# rtc.net
KiCad netlist of a schematic drawn in EAGLE
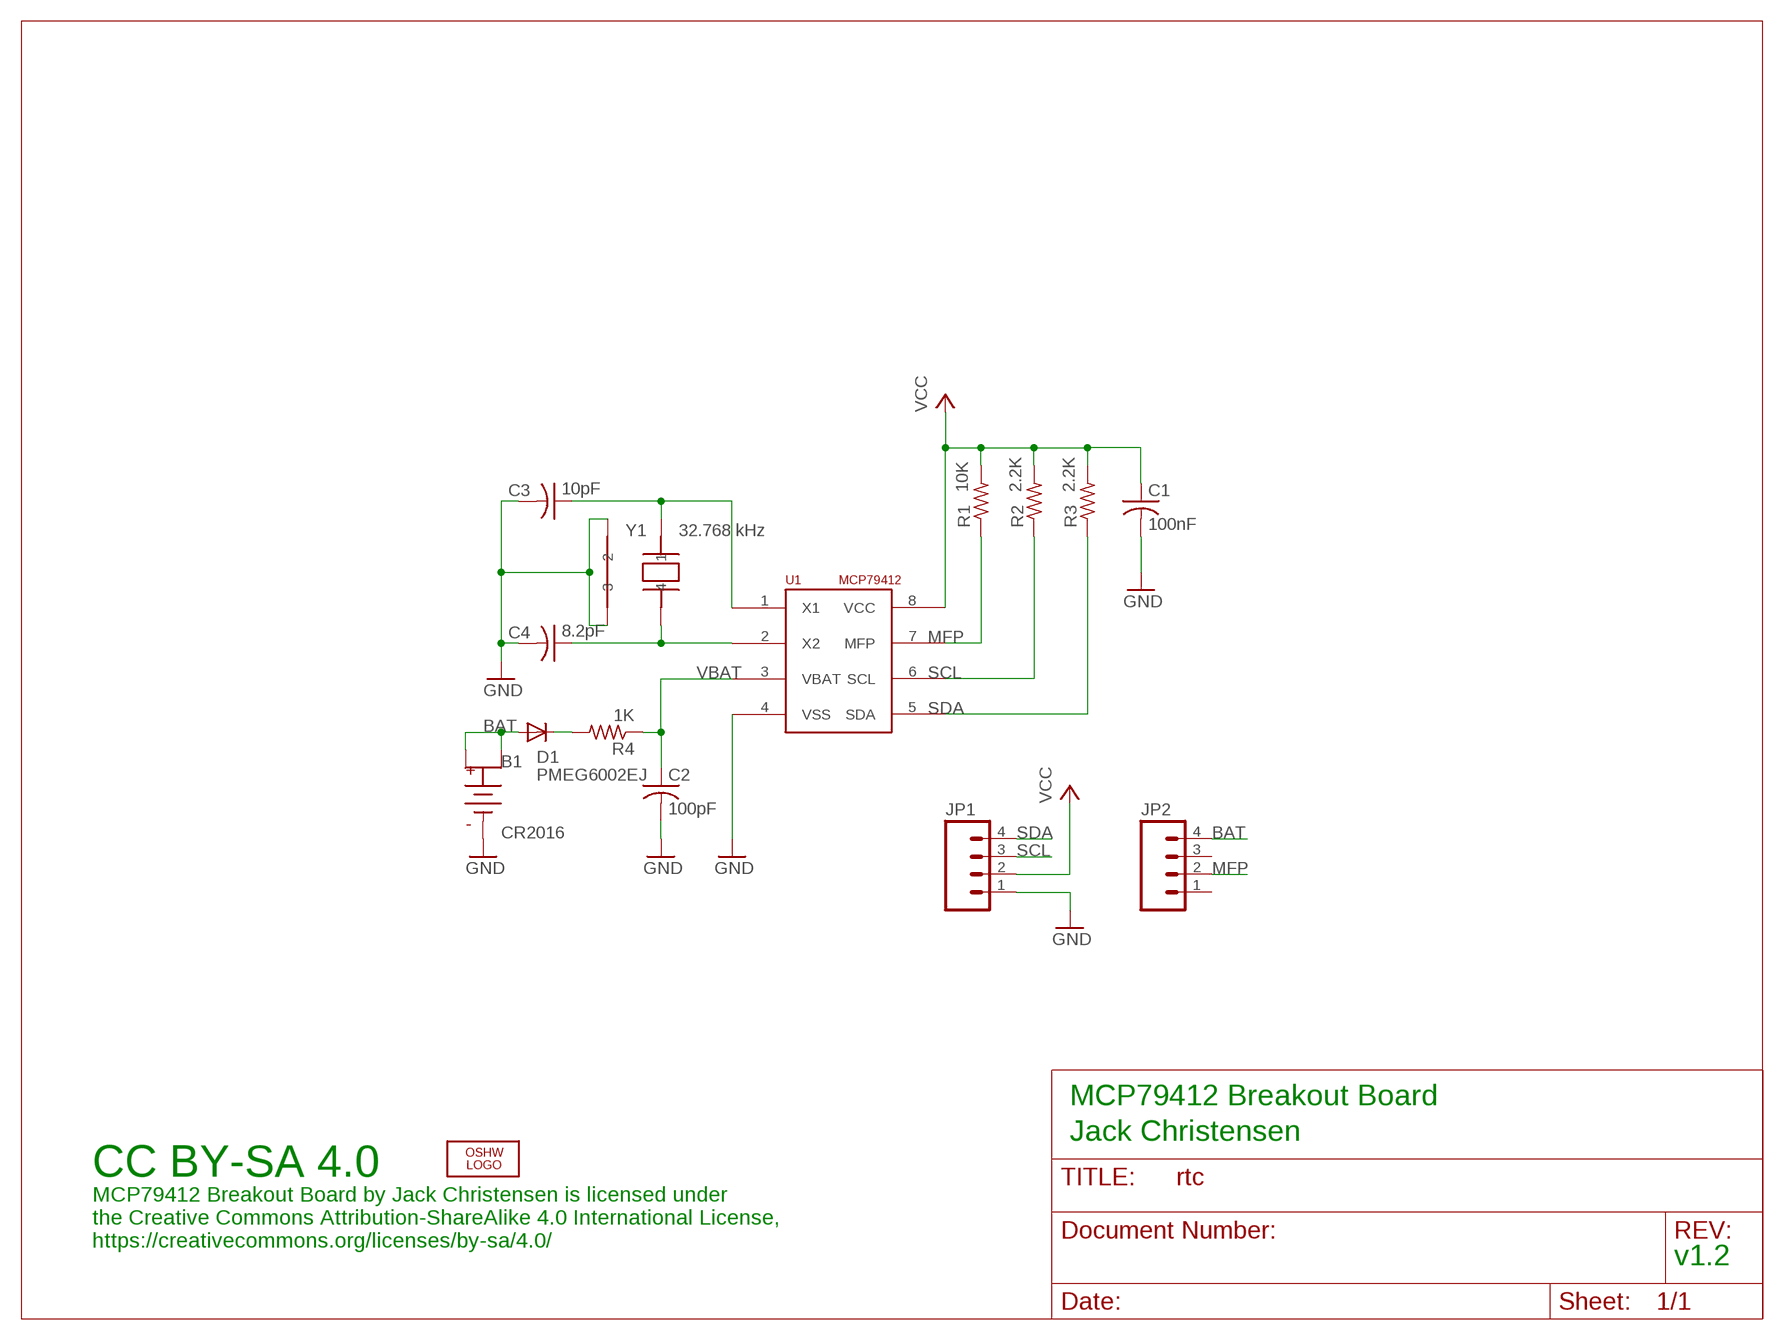
[diagram p0: schematic, sheet 1]

(export (version "E")
  (design (tool "Eeschema 10.0.6"))
  (components
    (comp (ref "B1")
      (value "CR2016")
      (footprint "eagle-import:BAT-HLD-002-SMT")
      (libsource (lib "eagle-import") (part "COIN-CELL-2016-SMT"))
    )
    (comp (ref "C1")
      (value "100nF")
      (footprint "eagle-import:M0805")
      (libsource (lib "eagle-import") (part "C-USM0805"))
    )
    (comp (ref "C2")
      (value "100pF")
      (footprint "eagle-import:M0805")
      (libsource (lib "eagle-import") (part "C-USM0805"))
    )
    (comp (ref "C3")
      (value "10pF")
      (footprint "eagle-import:M0805")
      (libsource (lib "eagle-import") (part "C-USM0805"))
    )
    (comp (ref "C4")
      (value "8.2pF")
      (footprint "eagle-import:M0805")
      (libsource (lib "eagle-import") (part "C-USM0805"))
    )
    (comp (ref "D1")
      (value "PMEG6002EJ")
      (footprint "eagle-import:SOD-323F-A")
      (libsource (lib "eagle-import") (part "DIODESOD-323F-A"))
    )
    (comp (ref "JP1")
      (value "M04LOCK")
      (footprint "eagle-import:1X04_LOCK")
      (libsource (lib "eagle-import") (part "M04LOCK"))
    )
    (comp (ref "JP2")
      (value "M04LOCK")
      (footprint "eagle-import:1X04_LOCK")
      (libsource (lib "eagle-import") (part "M04LOCK"))
    )
    (comp (ref "LOGO2")
      (value "OSHW_LOGO_8MILX0150-NT")
      (footprint "eagle-import:OSHW_8X150_NOTEXT")
      (libsource (lib "eagle-import") (part "OSHW_LOGO_8MILX0150-NT"))
    )
    (comp (ref "R1")
      (value "10K")
      (footprint "eagle-import:M0805")
      (libsource (lib "eagle-import") (part "R-US_M0805"))
    )
    (comp (ref "R2")
      (value "2.2K")
      (footprint "eagle-import:M0805")
      (libsource (lib "eagle-import") (part "R-US_M0805"))
    )
    (comp (ref "R3")
      (value "2.2K")
      (footprint "eagle-import:M0805")
      (libsource (lib "eagle-import") (part "R-US_M0805"))
    )
    (comp (ref "R4")
      (value "1K")
      (footprint "eagle-import:M0805")
      (libsource (lib "eagle-import") (part "R-US_M0805"))
    )
    (comp (ref "U1")
      (value "MCP79412")
      (footprint "eagle-import:SO08")
      (libsource (lib "eagle-import") (part "MCP7941X-SOIC-8"))
    )
    (comp (ref "Y1")
      (value "32.768 kHz")
      (footprint "eagle-import:CRYSTAL-CITIZEN-CM2XXC")
      (libsource (lib "eagle-import") (part "CRYSTAL-CITIZEN-CM2XXC"))
    )
  )
  (nets
    (net (code "1") (name "/BAT") (class "Default")
      (node (ref "B1") (pin "POS1") (pinfunction "POS1_POS1") (pintype "passive"))
      (node (ref "B1") (pin "POS2") (pinfunction "POS2_POS2") (pintype "passive"))
      (node (ref "D1") (pin "A") (pinfunction "A_A") (pintype "passive"))
      (node (ref "JP2") (pin "4") (pinfunction "4_4") (pintype "passive"))
    )
    (net (code "2") (name "/MFP") (class "Default")
      (node (ref "JP2") (pin "2") (pinfunction "2_2") (pintype "passive"))
      (node (ref "R1") (pin "1") (pinfunction "1_1") (pintype "passive"))
      (node (ref "U1") (pin "7") (pinfunction "MFP_7") (pintype "passive"))
    )
    (net (code "3") (name "/SCL") (class "Default")
      (node (ref "JP1") (pin "3") (pinfunction "3_3") (pintype "passive"))
      (node (ref "R2") (pin "1") (pinfunction "1_1") (pintype "passive"))
      (node (ref "U1") (pin "6") (pinfunction "SCL_6") (pintype "passive"))
    )
    (net (code "4") (name "/SDA") (class "Default")
      (node (ref "JP1") (pin "4") (pinfunction "4_4") (pintype "passive"))
      (node (ref "R3") (pin "1") (pinfunction "1_1") (pintype "passive"))
      (node (ref "U1") (pin "5") (pinfunction "SDA_5") (pintype "passive"))
    )
    (net (code "5") (name "/VBAT") (class "Default")
      (node (ref "C2") (pin "1") (pinfunction "1_1") (pintype "passive"))
      (node (ref "R4") (pin "1") (pinfunction "1_1") (pintype "passive"))
      (node (ref "U1") (pin "3") (pinfunction "VBAT_3") (pintype "passive"))
    )
    (net (code "6") (name "GND") (class "Default")
      (node (ref "B1") (pin "NEG") (pinfunction "B-_NEG") (pintype "passive"))
      (node (ref "C1") (pin "2") (pinfunction "2_2") (pintype "passive"))
      (node (ref "C2") (pin "2") (pinfunction "2_2") (pintype "passive"))
      (node (ref "C3") (pin "2") (pinfunction "2_2") (pintype "passive"))
      (node (ref "C4") (pin "2") (pinfunction "2_2") (pintype "passive"))
      (node (ref "JP1") (pin "1") (pinfunction "1_1") (pintype "passive"))
      (node (ref "U1") (pin "4") (pinfunction "VSS_4") (pintype "passive"))
      (node (ref "Y1") (pin "P$2") (pinfunction "2_P$2") (pintype "passive"))
      (node (ref "Y1") (pin "P$3") (pinfunction "3_P$3") (pintype "passive"))
    )
    (net (code "7") (name "Net-(D1-PadK)") (class "Default")
      (node (ref "D1") (pin "K") (pinfunction "K_K") (pintype "passive"))
      (node (ref "R4") (pin "2") (pinfunction "2_2") (pintype "passive"))
    )
    (net (code "8") (name "Net-(U1-X1)") (class "Default")
      (node (ref "C3") (pin "1") (pinfunction "1_1") (pintype "passive"))
      (node (ref "U1") (pin "1") (pinfunction "X1_1") (pintype "passive"))
      (node (ref "Y1") (pin "P$1") (pinfunction "1_P$1") (pintype "passive"))
    )
    (net (code "9") (name "Net-(U1-X2)") (class "Default")
      (node (ref "C4") (pin "1") (pinfunction "1_1") (pintype "passive"))
      (node (ref "U1") (pin "2") (pinfunction "X2_2") (pintype "passive"))
      (node (ref "Y1") (pin "P$4") (pinfunction "4_P$4") (pintype "passive"))
    )
    (net (code "10") (name "VCC") (class "Default")
      (node (ref "C1") (pin "1") (pinfunction "1_1") (pintype "passive"))
      (node (ref "JP1") (pin "2") (pinfunction "2_2") (pintype "passive"))
      (node (ref "R1") (pin "2") (pinfunction "2_2") (pintype "passive"))
      (node (ref "R2") (pin "2") (pinfunction "2_2") (pintype "passive"))
      (node (ref "R3") (pin "2") (pinfunction "2_2") (pintype "passive"))
      (node (ref "U1") (pin "8") (pinfunction "VCC_8") (pintype "passive"))
    )
    (net (code "11") (name "unconnected-(JP2-Pad1)") (class "Default")
      (node (ref "JP2") (pin "1") (pinfunction "1_1") (pintype "passive"))
    )
    (net (code "12") (name "unconnected-(JP2-Pad3)") (class "Default")
      (node (ref "JP2") (pin "3") (pinfunction "3_3") (pintype "passive"))
    )
  )
)
